# SPv2_1.net
KiCad netlist of a schematic drawn in EAGLE
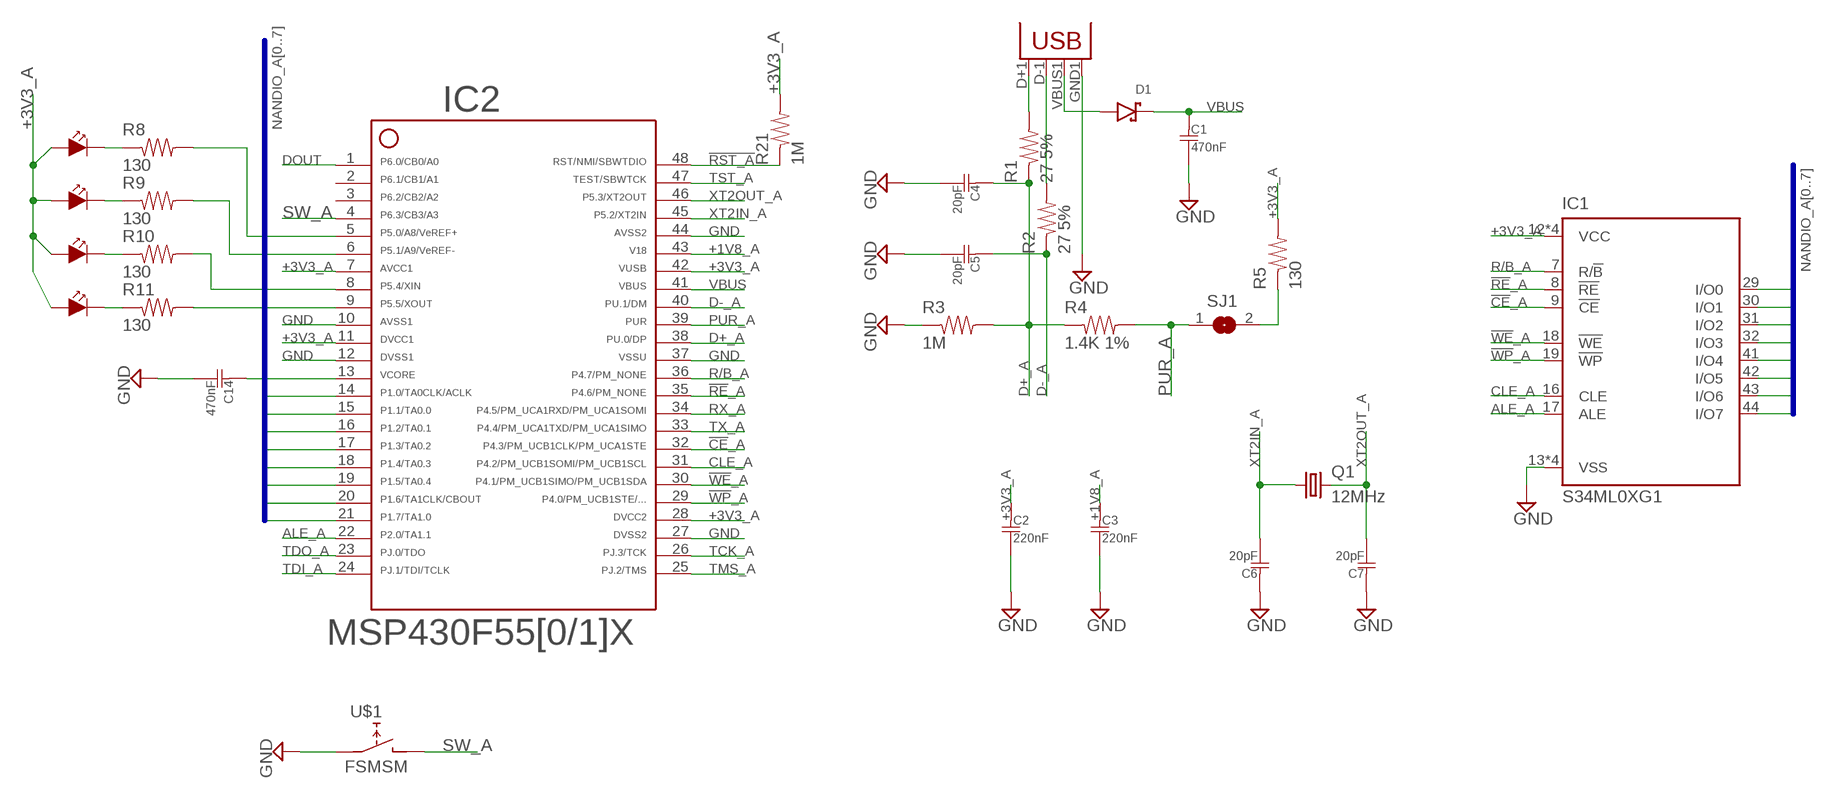
[diagram p0: schematic, sheet 1]
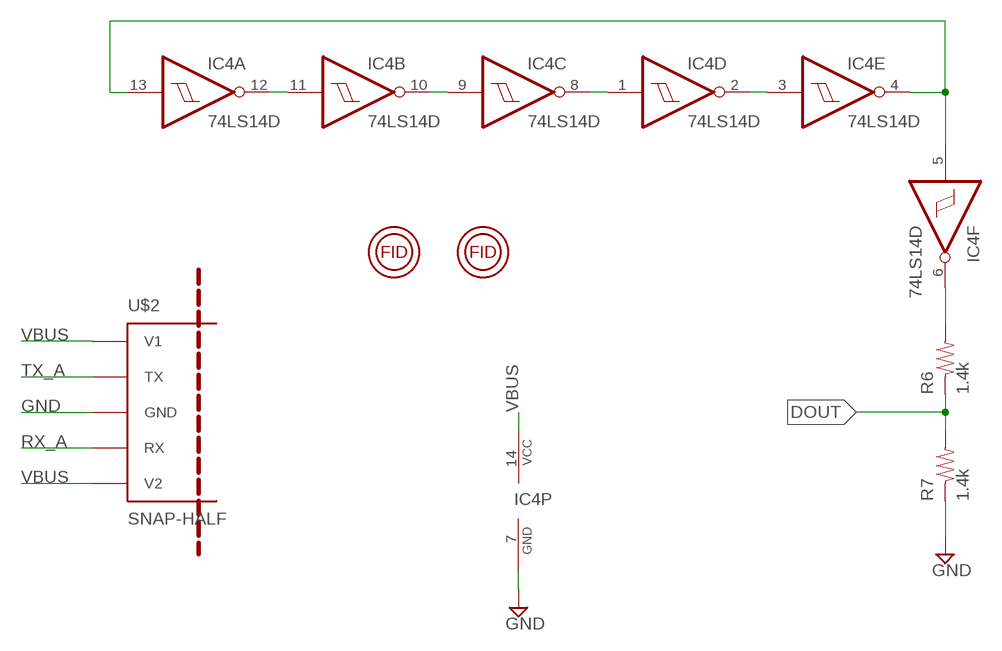
[diagram p1: schematic, sheet 2]

(export (version "E")
  (design (tool "Eeschema 10.0.6"))
  (components
    (comp (ref "IC4")
      (value "74LS14D")
      (footprint "eagle-import:SO14")
      (libsource (lib "eagle-import") (part "7414DLS"))
    )
    (comp (ref "R6")
      (value "1.4k")
      (footprint "eagle-import:R0805")
      (libsource (lib "eagle-import") (part "R0805"))
    )
    (comp (ref "R7")
      (value "1.4k")
      (footprint "eagle-import:R0805")
      (libsource (lib "eagle-import") (part "R0805"))
    )
    (comp (ref "U$2")
      (value "SNAP-HALF")
      (footprint "eagle-import:SNAP-HALF")
      (libsource (lib "eagle-import") (part "SNAP-HALF"))
    )
    (comp (ref "U$3")
      (value "FIDUCAL")
      (footprint "eagle-import:FIDUCAL")
      (libsource (lib "eagle-import") (part "FIDUCAL"))
    )
    (comp (ref "U$12")
      (value "FIDUCAL")
      (footprint "eagle-import:FIDUCAL")
      (libsource (lib "eagle-import") (part "FIDUCAL"))
    )
    (comp (ref "C1")
      (value "470nF")
      (footprint "eagle-import:R0805")
      (libsource (lib "eagle-import") (part "C0805"))
    )
    (comp (ref "C2")
      (value "220nF")
      (footprint "eagle-import:R0805")
      (libsource (lib "eagle-import") (part "C0805"))
    )
    (comp (ref "C3")
      (value "220nF")
      (footprint "eagle-import:R0805")
      (libsource (lib "eagle-import") (part "C0805"))
    )
    (comp (ref "C4")
      (value "20pF")
      (footprint "eagle-import:R0805")
      (libsource (lib "eagle-import") (part "C0805"))
    )
    (comp (ref "C5")
      (value "20pF")
      (footprint "eagle-import:R0805")
      (libsource (lib "eagle-import") (part "C0805"))
    )
    (comp (ref "C6")
      (value "20pF")
      (footprint "eagle-import:R0805")
      (libsource (lib "eagle-import") (part "C0805"))
    )
    (comp (ref "C7")
      (value "20pF")
      (footprint "eagle-import:R0805")
      (libsource (lib "eagle-import") (part "C0805"))
    )
    (comp (ref "C14")
      (value "470nF")
      (footprint "eagle-import:R0805")
      (libsource (lib "eagle-import") (part "C0805"))
    )
    (comp (ref "D1")
      (value "D-SCHOTTKY")
      (footprint "eagle-import:SOD123")
      (libsource (lib "eagle-import") (part "D-SCHOTTKY"))
    )
    (comp (ref "IC1")
      (value "S34ML0XG1")
      (footprint "eagle-import:TSOP48")
      (libsource (lib "eagle-import") (part "S34ML0XG1"))
    )
    (comp (ref "IC2")
      (value "F5508")
      (footprint "eagle-import:PT48")
      (libsource (lib "eagle-import") (part "F55[0/1]X---PT48"))
    )
    (comp (ref "JP1")
      (value "USBA-SMD-MALE")
      (footprint "eagle-import:USB-A-SMT-MALE")
      (libsource (lib "eagle-import") (part "USBA-SMD-MALE"))
    )
    (comp (ref "Q1")
      (value "12MHz")
      (footprint "eagle-import:CSM-3X")
      (libsource (lib "eagle-import") (part "CRYSTALCSM-3X"))
    )
    (comp (ref "R1")
      (value "27 5%")
      (footprint "eagle-import:R0805")
      (libsource (lib "eagle-import") (part "R0805"))
    )
    (comp (ref "R2")
      (value "27 5%")
      (footprint "eagle-import:R0805")
      (libsource (lib "eagle-import") (part "R0805"))
    )
    (comp (ref "R3")
      (value "1M")
      (footprint "eagle-import:R0805")
      (libsource (lib "eagle-import") (part "R0805"))
    )
    (comp (ref "R4")
      (value "1.4K 1%")
      (footprint "eagle-import:R0805")
      (libsource (lib "eagle-import") (part "R0805"))
    )
    (comp (ref "R5")
      (value "130")
      (footprint "eagle-import:R0805")
      (libsource (lib "eagle-import") (part "R0805"))
    )
    (comp (ref "R8")
      (value "130")
      (footprint "eagle-import:R0805")
      (libsource (lib "eagle-import") (part "R0805"))
    )
    (comp (ref "R9")
      (value "130")
      (footprint "eagle-import:R0805")
      (libsource (lib "eagle-import") (part "R0805"))
    )
    (comp (ref "R10")
      (value "130")
      (footprint "eagle-import:R0805")
      (libsource (lib "eagle-import") (part "R0805"))
    )
    (comp (ref "R11")
      (value "130")
      (footprint "eagle-import:R0805")
      (libsource (lib "eagle-import") (part "R0805"))
    )
    (comp (ref "R21")
      (value "1M")
      (footprint "eagle-import:R0805")
      (libsource (lib "eagle-import") (part "R0805"))
    )
    (comp (ref "SJ1")
      (value "SJW")
      (footprint "eagle-import:SJW")
      (libsource (lib "eagle-import") (part "SJW"))
    )
    (comp (ref "U$1")
      (value "FSMSM")
      (footprint "eagle-import:FSMSM")
      (libsource (lib "eagle-import") (part "FSMSM"))
    )
    (comp (ref "U$5")
      (value "LED")
      (footprint "eagle-import:LED0805")
      (libsource (lib "eagle-import") (part "LED"))
    )
    (comp (ref "U$6")
      (value "LED")
      (footprint "eagle-import:LED0805")
      (libsource (lib "eagle-import") (part "LED"))
    )
    (comp (ref "U$7")
      (value "LED")
      (footprint "eagle-import:LED0805")
      (libsource (lib "eagle-import") (part "LED"))
    )
    (comp (ref "U$8")
      (value "LED")
      (footprint "eagle-import:LED0805")
      (libsource (lib "eagle-import") (part "LED"))
    )
  )
  (nets
    (net (code "1") (name "+1V8_A") (class "Default")
      (node (ref "C3") (pin "P$1") (pinfunction "1_P$1") (pintype "passive"))
      (node (ref "IC2") (pin "43") (pinfunction "43_43") (pintype "power_in"))
    )
    (net (code "2") (name "+3V3_A") (class "Default")
      (node (ref "C2") (pin "P$1") (pinfunction "1_P$1") (pintype "passive"))
      (node (ref "IC1") (pin "12") (pinfunction "VCC_12") (pintype "power_in"))
      (node (ref "IC1") (pin "34") (pinfunction "VCC_34") (pintype "power_in"))
      (node (ref "IC1") (pin "37") (pinfunction "VCC_37") (pintype "power_in"))
      (node (ref "IC1") (pin "39") (pinfunction "VCC_39") (pintype "power_in"))
      (node (ref "IC2") (pin "11") (pinfunction "11_11") (pintype "power_in"))
      (node (ref "IC2") (pin "28") (pinfunction "28_28") (pintype "power_in"))
      (node (ref "IC2") (pin "42") (pinfunction "42_42") (pintype "power_in"))
      (node (ref "IC2") (pin "7") (pinfunction "7_7") (pintype "power_in"))
      (node (ref "R21") (pin "P$2") (pinfunction "2_P$2") (pintype "passive"))
      (node (ref "R5") (pin "P$2") (pinfunction "2_P$2") (pintype "passive"))
      (node (ref "U$5") (pin "ANODE") (pinfunction "ANODE_ANODE") (pintype "passive"))
      (node (ref "U$6") (pin "ANODE") (pinfunction "ANODE_ANODE") (pintype "passive"))
      (node (ref "U$7") (pin "ANODE") (pinfunction "ANODE_ANODE") (pintype "passive"))
      (node (ref "U$8") (pin "ANODE") (pinfunction "ANODE_ANODE") (pintype "passive"))
    )
    (net (code "4") (name "ALE_A") (class "Default")
      (node (ref "IC1") (pin "17") (pinfunction "ALE_17") (pintype "input"))
      (node (ref "IC2") (pin "22") (pinfunction "22_22") (pintype "bidirectional"))
    )
    (net (code "5") (name "CLE_A") (class "Default")
      (node (ref "IC1") (pin "16") (pinfunction "CLE_16") (pintype "input"))
      (node (ref "IC2") (pin "31") (pinfunction "31_31") (pintype "bidirectional"))
    )
    (net (code "6") (name "D+_A") (class "Default")
      (node (ref "C4") (pin "P$1") (pinfunction "1_P$1") (pintype "passive"))
      (node (ref "IC2") (pin "38") (pinfunction "38_38") (pintype "bidirectional"))
      (node (ref "R1") (pin "P$1") (pinfunction "1_P$1") (pintype "passive"))
      (node (ref "R3") (pin "P$2") (pinfunction "2_P$2") (pintype "passive"))
      (node (ref "R4") (pin "P$1") (pinfunction "1_P$1") (pintype "passive"))
    )
    (net (code "7") (name "D-_A") (class "Default")
      (node (ref "C5") (pin "P$1") (pinfunction "1_P$1") (pintype "passive"))
      (node (ref "IC2") (pin "40") (pinfunction "40_40") (pintype "bidirectional"))
      (node (ref "R2") (pin "P$1") (pinfunction "1_P$1") (pintype "passive"))
    )
    (net (code "8") (name "DOUT") (class "Default")
      (node (ref "IC2") (pin "1") (pinfunction "1_1") (pintype "bidirectional"))
      (node (ref "R6") (pin "P$1") (pinfunction "1_P$1") (pintype "passive"))
      (node (ref "R7") (pin "P$2") (pinfunction "2_P$2") (pintype "passive"))
    )
    (net (code "9") (name "GND") (class "Default")
      (node (ref "C1") (pin "P$2") (pinfunction "2_P$2") (pintype "passive"))
      (node (ref "C14") (pin "P$2") (pinfunction "2_P$2") (pintype "passive"))
      (node (ref "C2") (pin "P$2") (pinfunction "2_P$2") (pintype "passive"))
      (node (ref "C3") (pin "P$2") (pinfunction "2_P$2") (pintype "passive"))
      (node (ref "C4") (pin "P$2") (pinfunction "2_P$2") (pintype "passive"))
      (node (ref "C5") (pin "P$2") (pinfunction "2_P$2") (pintype "passive"))
      (node (ref "C6") (pin "P$1") (pinfunction "1_P$1") (pintype "passive"))
      (node (ref "C7") (pin "P$1") (pinfunction "1_P$1") (pintype "passive"))
      (node (ref "IC1") (pin "13") (pinfunction "VSS_13") (pintype "power_in"))
      (node (ref "IC1") (pin "25") (pinfunction "VSS_25") (pintype "power_in"))
      (node (ref "IC1") (pin "36") (pinfunction "VSS_36") (pintype "power_in"))
      (node (ref "IC1") (pin "48") (pinfunction "VSS_48") (pintype "power_in"))
      (node (ref "IC2") (pin "10") (pinfunction "10_10") (pintype "power_in"))
      (node (ref "IC2") (pin "12") (pinfunction "12_12") (pintype "power_in"))
      (node (ref "IC2") (pin "27") (pinfunction "27_27") (pintype "power_in"))
      (node (ref "IC2") (pin "37") (pinfunction "37_37") (pintype "power_in"))
      (node (ref "IC2") (pin "44") (pinfunction "44_44") (pintype "power_in"))
      (node (ref "IC4") (pin "7") (pinfunction "GND_7") (pintype "power_in"))
      (node (ref "JP1") (pin "GND1") (pinfunction "GND_GND1") (pintype "bidirectional"))
      (node (ref "R3") (pin "P$1") (pinfunction "1_P$1") (pintype "passive"))
      (node (ref "R7") (pin "P$1") (pinfunction "1_P$1") (pintype "passive"))
      (node (ref "U$1") (pin "P$1") (pinfunction "A1_P$1") (pintype "passive"))
      (node (ref "U$2") (pin "P$3") (pinfunction "GND_P$3") (pintype "bidirectional"))
    )
    (net (code "10") (name "NANDIO_A0") (class "Default")
      (node (ref "IC1") (pin "29") (pinfunction "I/O0_29") (pintype "bidirectional"))
      (node (ref "IC2") (pin "14") (pinfunction "14_14") (pintype "bidirectional"))
    )
    (net (code "11") (name "NANDIO_A1") (class "Default")
      (node (ref "IC1") (pin "30") (pinfunction "I/O1_30") (pintype "bidirectional"))
      (node (ref "IC2") (pin "15") (pinfunction "15_15") (pintype "bidirectional"))
    )
    (net (code "12") (name "NANDIO_A2") (class "Default")
      (node (ref "IC1") (pin "31") (pinfunction "I/O2_31") (pintype "bidirectional"))
      (node (ref "IC2") (pin "16") (pinfunction "16_16") (pintype "bidirectional"))
    )
    (net (code "13") (name "NANDIO_A3") (class "Default")
      (node (ref "IC1") (pin "32") (pinfunction "I/O3_32") (pintype "bidirectional"))
      (node (ref "IC2") (pin "17") (pinfunction "17_17") (pintype "bidirectional"))
    )
    (net (code "14") (name "NANDIO_A4") (class "Default")
      (node (ref "IC1") (pin "41") (pinfunction "I/O4_41") (pintype "bidirectional"))
      (node (ref "IC2") (pin "18") (pinfunction "18_18") (pintype "bidirectional"))
    )
    (net (code "15") (name "NANDIO_A5") (class "Default")
      (node (ref "IC1") (pin "42") (pinfunction "I/O5_42") (pintype "bidirectional"))
      (node (ref "IC2") (pin "19") (pinfunction "19_19") (pintype "bidirectional"))
    )
    (net (code "16") (name "NANDIO_A6") (class "Default")
      (node (ref "IC1") (pin "43") (pinfunction "I/O6_43") (pintype "bidirectional"))
      (node (ref "IC2") (pin "20") (pinfunction "20_20") (pintype "bidirectional"))
    )
    (net (code "17") (name "NANDIO_A7") (class "Default")
      (node (ref "IC1") (pin "44") (pinfunction "I/O7_44") (pintype "bidirectional"))
      (node (ref "IC2") (pin "21") (pinfunction "21_21") (pintype "bidirectional"))
    )
    (net (code "18") (name "Net-(C14-1)") (class "Default")
      (node (ref "C14") (pin "P$1") (pinfunction "1_P$1") (pintype "passive"))
      (node (ref "IC2") (pin "13") (pinfunction "13_13") (pintype "power_in"))
    )
    (net (code "19") (name "Net-(IC4A-I)") (class "Default")
      (node (ref "IC4") (pin "13") (pinfunction "I_13") (pintype "input"))
      (node (ref "IC4") (pin "4") (pinfunction "O_4") (pintype "output"))
      (node (ref "IC4") (pin "5") (pinfunction "I_5") (pintype "input"))
    )
    (net (code "20") (name "Net-(IC4A-O)") (class "Default")
      (node (ref "IC4") (pin "11") (pinfunction "I_11") (pintype "input"))
      (node (ref "IC4") (pin "12") (pinfunction "O_12") (pintype "output"))
    )
    (net (code "21") (name "Net-(IC4B-O)") (class "Default")
      (node (ref "IC4") (pin "10") (pinfunction "O_10") (pintype "output"))
      (node (ref "IC4") (pin "9") (pinfunction "I_9") (pintype "input"))
    )
    (net (code "22") (name "Net-(IC4C-O)") (class "Default")
      (node (ref "IC4") (pin "1") (pinfunction "I_1") (pintype "input"))
      (node (ref "IC4") (pin "8") (pinfunction "O_8") (pintype "output"))
    )
    (net (code "23") (name "Net-(IC4D-O)") (class "Default")
      (node (ref "IC4") (pin "2") (pinfunction "O_2") (pintype "output"))
      (node (ref "IC4") (pin "3") (pinfunction "I_3") (pintype "input"))
    )
    (net (code "24") (name "Net-(IC4F-O)") (class "Default")
      (node (ref "IC4") (pin "6") (pinfunction "O_6") (pintype "output"))
      (node (ref "R6") (pin "P$2") (pinfunction "2_P$2") (pintype "passive"))
    )
    (net (code "25") (name "Net-(JP1-D+)") (class "Default")
      (node (ref "JP1") (pin "D+1") (pinfunction "D+_D+1") (pintype "bidirectional"))
      (node (ref "R1") (pin "P$2") (pinfunction "2_P$2") (pintype "passive"))
    )
    (net (code "26") (name "Net-(JP1-D-)") (class "Default")
      (node (ref "JP1") (pin "D-1") (pinfunction "D-_D-1") (pintype "bidirectional"))
      (node (ref "R2") (pin "P$2") (pinfunction "2_P$2") (pintype "passive"))
    )
    (net (code "27") (name "Net-(JP1-VBUS)") (class "Default")
      (node (ref "D1") (pin "ANODE") (pinfunction "ANODE_ANODE") (pintype "passive"))
      (node (ref "JP1") (pin "VBUS1") (pinfunction "VBUS_VBUS1") (pintype "bidirectional"))
    )
    (net (code "28") (name "Net-(R5-1)") (class "Default")
      (node (ref "R5") (pin "P$1") (pinfunction "1_P$1") (pintype "passive"))
      (node (ref "SJ1") (pin "2") (pinfunction "2_2") (pintype "passive"))
    )
    (net (code "29") (name "Net-(R8-1)") (class "Default")
      (node (ref "R8") (pin "P$1") (pinfunction "1_P$1") (pintype "passive"))
      (node (ref "U$5") (pin "CATHODE") (pinfunction "CATHODE_CATHODE") (pintype "passive"))
    )
    (net (code "30") (name "Net-(R8-2)") (class "Default")
      (node (ref "IC2") (pin "5") (pinfunction "5_5") (pintype "bidirectional"))
      (node (ref "R8") (pin "P$2") (pinfunction "2_P$2") (pintype "passive"))
    )
    (net (code "31") (name "Net-(R9-1)") (class "Default")
      (node (ref "R9") (pin "P$1") (pinfunction "1_P$1") (pintype "passive"))
      (node (ref "U$6") (pin "CATHODE") (pinfunction "CATHODE_CATHODE") (pintype "passive"))
    )
    (net (code "32") (name "Net-(R9-2)") (class "Default")
      (node (ref "IC2") (pin "6") (pinfunction "6_6") (pintype "bidirectional"))
      (node (ref "R9") (pin "P$2") (pinfunction "2_P$2") (pintype "passive"))
    )
    (net (code "33") (name "Net-(R10-1)") (class "Default")
      (node (ref "R10") (pin "P$1") (pinfunction "1_P$1") (pintype "passive"))
      (node (ref "U$7") (pin "CATHODE") (pinfunction "CATHODE_CATHODE") (pintype "passive"))
    )
    (net (code "34") (name "Net-(R10-2)") (class "Default")
      (node (ref "IC2") (pin "8") (pinfunction "8_8") (pintype "bidirectional"))
      (node (ref "R10") (pin "P$2") (pinfunction "2_P$2") (pintype "passive"))
    )
    (net (code "35") (name "Net-(R11-1)") (class "Default")
      (node (ref "R11") (pin "P$1") (pinfunction "1_P$1") (pintype "passive"))
      (node (ref "U$8") (pin "CATHODE") (pinfunction "CATHODE_CATHODE") (pintype "passive"))
    )
    (net (code "36") (name "Net-(R11-2)") (class "Default")
      (node (ref "IC2") (pin "9") (pinfunction "9_9") (pintype "bidirectional"))
      (node (ref "R11") (pin "P$2") (pinfunction "2_P$2") (pintype "passive"))
    )
    (net (code "37") (name "PUR_A") (class "Default")
      (node (ref "IC2") (pin "39") (pinfunction "39_39") (pintype "bidirectional"))
      (node (ref "R4") (pin "P$2") (pinfunction "2_P$2") (pintype "passive"))
      (node (ref "SJ1") (pin "1") (pinfunction "1_1") (pintype "passive"))
    )
    (net (code "38") (name "RX_A") (class "Default")
      (node (ref "IC2") (pin "34") (pinfunction "34_34") (pintype "bidirectional"))
      (node (ref "U$2") (pin "P$4") (pinfunction "RX_P$4") (pintype "bidirectional"))
    )
    (net (code "39") (name "R{slash}B_A") (class "Default")
      (node (ref "IC1") (pin "7") (pinfunction "R/~{B}_7") (pintype "input"))
      (node (ref "IC2") (pin "36") (pinfunction "36_36") (pintype "bidirectional"))
    )
    (net (code "40") (name "SW_A") (class "Default")
      (node (ref "IC2") (pin "4") (pinfunction "4_4") (pintype "bidirectional"))
      (node (ref "U$1") (pin "P$2") (pinfunction "B_P$2") (pintype "passive"))
    )
    (net (code "41") (name "TCK_A") (class "Default")
      (node (ref "IC2") (pin "26") (pinfunction "26_26") (pintype "bidirectional"))
    )
    (net (code "42") (name "TDI_A") (class "Default")
      (node (ref "IC2") (pin "24") (pinfunction "24_24") (pintype "bidirectional"))
    )
    (net (code "43") (name "TDO_A") (class "Default")
      (node (ref "IC2") (pin "23") (pinfunction "23_23") (pintype "bidirectional"))
    )
    (net (code "44") (name "TMS_A") (class "Default")
      (node (ref "IC2") (pin "25") (pinfunction "25_25") (pintype "bidirectional"))
    )
    (net (code "45") (name "TST_A") (class "Default")
      (node (ref "IC2") (pin "47") (pinfunction "47_47") (pintype "input"))
    )
    (net (code "46") (name "TX_A") (class "Default")
      (node (ref "IC2") (pin "33") (pinfunction "33_33") (pintype "bidirectional"))
      (node (ref "U$2") (pin "P$2") (pinfunction "TX_P$2") (pintype "bidirectional"))
    )
    (net (code "47") (name "VBUS") (class "Default")
      (node (ref "C1") (pin "P$1") (pinfunction "1_P$1") (pintype "passive"))
      (node (ref "D1") (pin "CATHODE") (pinfunction "CATHODE_CATHODE") (pintype "passive"))
      (node (ref "IC2") (pin "41") (pinfunction "41_41") (pintype "power_in"))
      (node (ref "IC4") (pin "14") (pinfunction "VCC_14") (pintype "power_in"))
      (node (ref "U$2") (pin "P$1") (pinfunction "V1_P$1") (pintype "bidirectional"))
      (node (ref "U$2") (pin "P$5") (pinfunction "V2_P$5") (pintype "bidirectional"))
    )
    (net (code "48") (name "XT2IN_A") (class "Default")
      (node (ref "C6") (pin "P$2") (pinfunction "2_P$2") (pintype "passive"))
      (node (ref "IC2") (pin "45") (pinfunction "45_45") (pintype "bidirectional"))
      (node (ref "Q1") (pin "P$1") (pinfunction "1_P$1") (pintype "passive"))
    )
    (net (code "49") (name "XT2OUT_A") (class "Default")
      (node (ref "C7") (pin "P$2") (pinfunction "2_P$2") (pintype "passive"))
      (node (ref "IC2") (pin "46") (pinfunction "46_46") (pintype "power_in"))
      (node (ref "Q1") (pin "P$2") (pinfunction "2_P$2") (pintype "passive"))
    )
    (net (code "50") (name "unconnected-(IC2-Pad2)") (class "Default")
      (node (ref "IC2") (pin "2") (pinfunction "2_2") (pintype "bidirectional"))
    )
    (net (code "51") (name "unconnected-(IC2-Pad3)") (class "Default")
      (node (ref "IC2") (pin "3") (pinfunction "3_3") (pintype "bidirectional"))
    )
    (net (code "52") (name "~{CE}_A") (class "Default")
      (node (ref "IC1") (pin "9") (pinfunction "~{CE}_9") (pintype "input"))
      (node (ref "IC2") (pin "32") (pinfunction "32_32") (pintype "bidirectional"))
    )
    (net (code "53") (name "~{RE}_A") (class "Default")
      (node (ref "IC1") (pin "8") (pinfunction "~{RE}_8") (pintype "input"))
      (node (ref "IC2") (pin "35") (pinfunction "35_35") (pintype "bidirectional"))
    )
    (net (code "54") (name "~{RST_A}") (class "Default")
      (node (ref "IC2") (pin "48") (pinfunction "48_48") (pintype "bidirectional"))
      (node (ref "R21") (pin "P$1") (pinfunction "1_P$1") (pintype "passive"))
    )
    (net (code "55") (name "~{WE}_A") (class "Default")
      (node (ref "IC1") (pin "18") (pinfunction "~{WE}_18") (pintype "input"))
      (node (ref "IC2") (pin "30") (pinfunction "30_30") (pintype "bidirectional"))
    )
    (net (code "56") (name "~{WP}_A") (class "Default")
      (node (ref "IC1") (pin "19") (pinfunction "~{WP}_19") (pintype "input"))
      (node (ref "IC2") (pin "29") (pinfunction "29_29") (pintype "bidirectional"))
    )
  )
)
